# Sheet1.net
KiCad netlist of a schematic drawn in Altium Designer
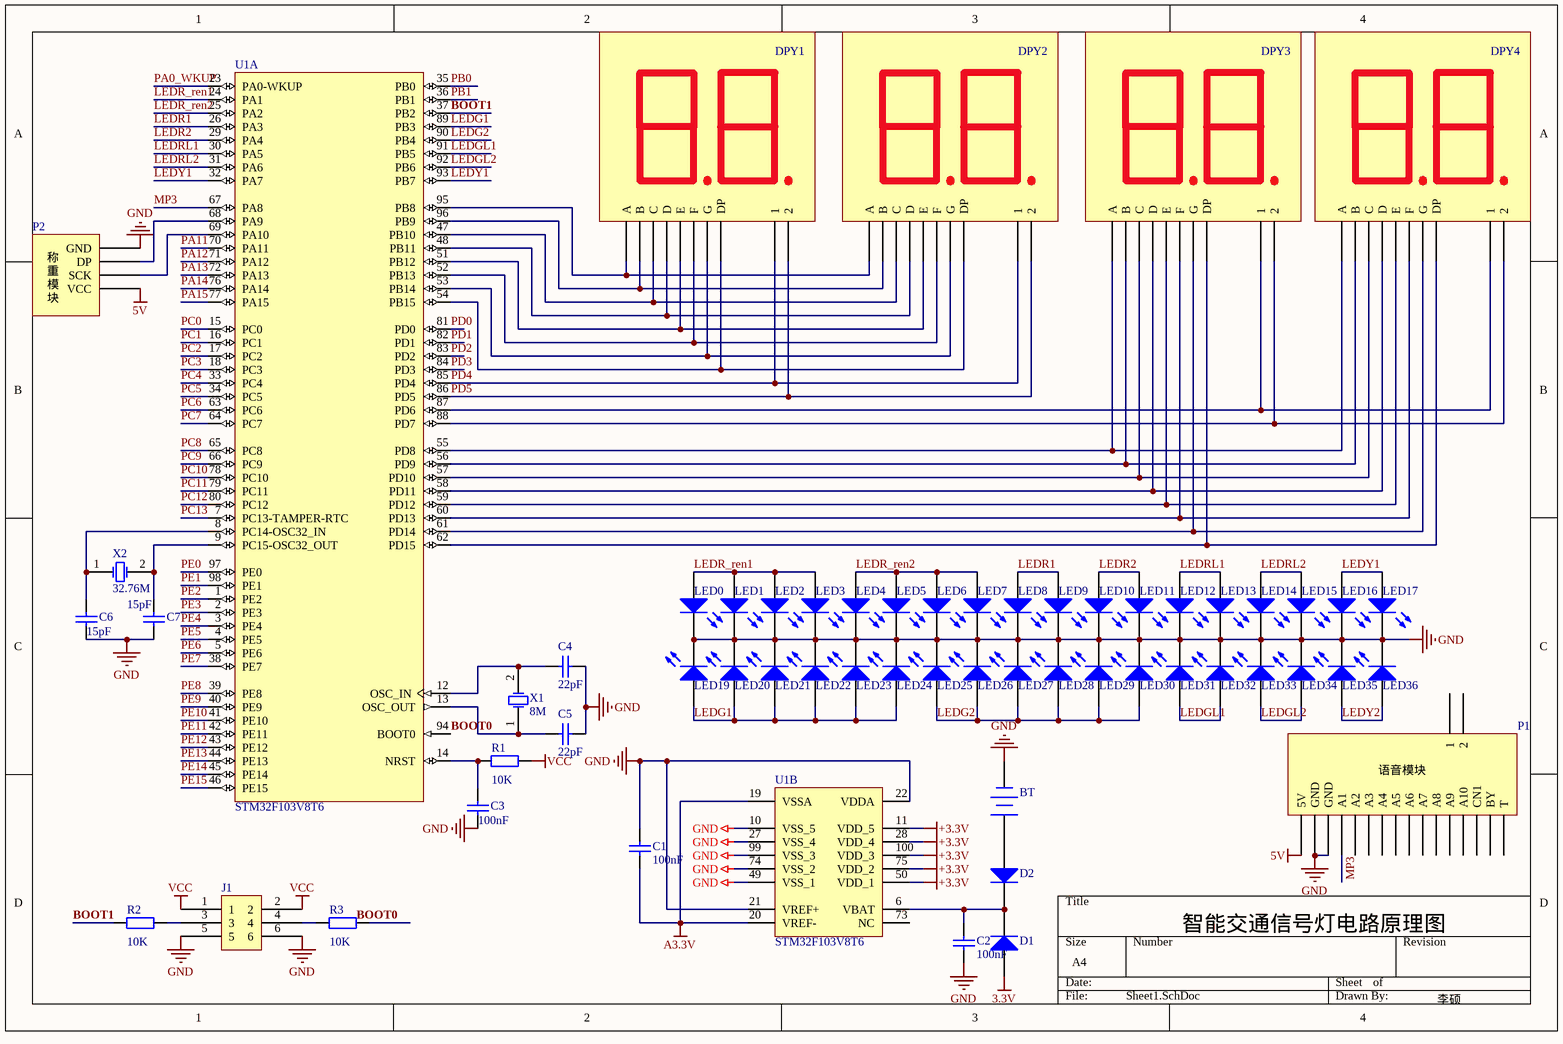
[diagram p0: Sheet1.SchDoc]

(export (version "E")
  (design (tool "Eeschema 10.0.6"))
  (components
    (comp (ref "BT")
      (value "Battery")
      (footprint "BAT-2")
      (description "Multicell Battery")
      (fields (field (name "PUBLISHER") "Altium Limited"))
      (libsource (lib "Miscellaneous Devices") (part "Battery"))
    )
    (comp (ref "C1")
      (value "100nF")
      (footprint "RAD-0.3")
      (description "Capacitor")
      (fields (field (name "Comment") "Cap") (field (name "PUBLISHER") "Altium Limited"))
      (libsource (lib "Miscellaneous Devices") (part "Cap"))
    )
    (comp (ref "C2")
      (value "100nF")
      (footprint "RAD-0.3")
      (description "Capacitor")
      (fields (field (name "Comment") "Cap") (field (name "PUBLISHER") "Altium Limited"))
      (libsource (lib "Miscellaneous Devices") (part "Cap"))
    )
    (comp (ref "C3")
      (value "100nF")
      (footprint "RAD-0.3")
      (description "Capacitor")
      (fields (field (name "Comment") "Cap") (field (name "PUBLISHER") "Altium Limited"))
      (libsource (lib "Miscellaneous Devices") (part "Cap"))
    )
    (comp (ref "C4")
      (value "22pF")
      (footprint "RAD-0.3")
      (description "Capacitor")
      (fields (field (name "Comment") "Cap") (field (name "PUBLISHER") "Altium Limited"))
      (libsource (lib "Miscellaneous Devices") (part "Cap"))
    )
    (comp (ref "C5")
      (value "22pF")
      (footprint "RAD-0.3")
      (description "Capacitor")
      (fields (field (name "Comment") "Cap") (field (name "PUBLISHER") "Altium Limited"))
      (libsource (lib "Miscellaneous Devices") (part "Cap"))
    )
    (comp (ref "C6")
      (value "15pF")
      (footprint "RAD-0.3")
      (description "Capacitor")
      (fields (field (name "Comment") "Cap") (field (name "PUBLISHER") "Altium Limited"))
      (libsource (lib "Miscellaneous Devices") (part "Cap"))
    )
    (comp (ref "C7")
      (value "15pF")
      (footprint "RAD-0.3")
      (description "Capacitor")
      (fields (field (name "Comment") "Cap") (field (name "PUBLISHER") "Altium Limited"))
      (libsource (lib "Miscellaneous Devices") (part "Cap"))
    )
    (comp (ref "D1")
      (value "Diode")
      (footprint "DSO-C2/X3.3")
      (description "Default Diode")
      (fields (field (name "PUBLISHER") "Altium Limited"))
      (libsource (lib "Miscellaneous Devices") (part "Diode"))
    )
    (comp (ref "D2")
      (value "Diode")
      (footprint "DSO-C2/X3.3")
      (description "Default Diode")
      (fields (field (name "PUBLISHER") "Altium Limited"))
      (libsource (lib "Miscellaneous Devices") (part "Diode"))
    )
    (comp (ref "DPY1") (value "Component_1") (libsource (lib "Schlib1") (part "Component_1")))
    (comp (ref "DPY2") (value "Component_1") (libsource (lib "Schlib1") (part "Component_1")))
    (comp (ref "DPY3") (value "Component_1") (libsource (lib "Schlib1") (part "Component_1")))
    (comp (ref "DPY4") (value "Component_1") (libsource (lib "Schlib1") (part "Component_1")))
    (comp (ref "J1") (value "Component_1") (libsource (lib "") (part "Component_1_1")))
    (comp (ref "LED0")
      (value "LED0")
      (footprint "LED-0")
      (description "Typical INFRARED GaAs LED")
      (fields (field (name "PUBLISHER") "Altium Limited"))
      (libsource (lib "Miscellaneous Devices") (part "LED0"))
    )
    (comp (ref "LED1")
      (value "LED0")
      (footprint "LED-0")
      (description "Typical INFRARED GaAs LED")
      (fields (field (name "PUBLISHER") "Altium Limited"))
      (libsource (lib "Miscellaneous Devices") (part "LED0"))
    )
    (comp (ref "LED2")
      (value "LED0")
      (footprint "LED-0")
      (description "Typical INFRARED GaAs LED")
      (fields (field (name "PUBLISHER") "Altium Limited"))
      (libsource (lib "Miscellaneous Devices") (part "LED0"))
    )
    (comp (ref "LED3")
      (value "LED0")
      (footprint "LED-0")
      (description "Typical INFRARED GaAs LED")
      (fields (field (name "PUBLISHER") "Altium Limited"))
      (libsource (lib "Miscellaneous Devices") (part "LED0"))
    )
    (comp (ref "LED4")
      (value "LED0")
      (footprint "LED-0")
      (description "Typical INFRARED GaAs LED")
      (fields (field (name "PUBLISHER") "Altium Limited"))
      (libsource (lib "Miscellaneous Devices") (part "LED0"))
    )
    (comp (ref "LED5")
      (value "LED0")
      (footprint "LED-0")
      (description "Typical INFRARED GaAs LED")
      (fields (field (name "PUBLISHER") "Altium Limited"))
      (libsource (lib "Miscellaneous Devices") (part "LED0"))
    )
    (comp (ref "LED6")
      (value "LED0")
      (footprint "LED-0")
      (description "Typical INFRARED GaAs LED")
      (fields (field (name "PUBLISHER") "Altium Limited"))
      (libsource (lib "Miscellaneous Devices") (part "LED0"))
    )
    (comp (ref "LED7")
      (value "LED0")
      (footprint "LED-0")
      (description "Typical INFRARED GaAs LED")
      (fields (field (name "PUBLISHER") "Altium Limited"))
      (libsource (lib "Miscellaneous Devices") (part "LED0"))
    )
    (comp (ref "LED8")
      (value "LED0")
      (footprint "LED-0")
      (description "Typical INFRARED GaAs LED")
      (fields (field (name "PUBLISHER") "Altium Limited"))
      (libsource (lib "Miscellaneous Devices") (part "LED0"))
    )
    (comp (ref "LED9")
      (value "LED0")
      (footprint "LED-0")
      (description "Typical INFRARED GaAs LED")
      (fields (field (name "PUBLISHER") "Altium Limited"))
      (libsource (lib "Miscellaneous Devices") (part "LED0"))
    )
    (comp (ref "LED10")
      (value "LED0")
      (footprint "LED-0")
      (description "Typical INFRARED GaAs LED")
      (fields (field (name "PUBLISHER") "Altium Limited"))
      (libsource (lib "Miscellaneous Devices") (part "LED0"))
    )
    (comp (ref "LED11")
      (value "LED0")
      (footprint "LED-0")
      (description "Typical INFRARED GaAs LED")
      (fields (field (name "PUBLISHER") "Altium Limited"))
      (libsource (lib "Miscellaneous Devices") (part "LED0"))
    )
    (comp (ref "LED12")
      (value "LED0")
      (footprint "LED-0")
      (description "Typical INFRARED GaAs LED")
      (fields (field (name "PUBLISHER") "Altium Limited"))
      (libsource (lib "Miscellaneous Devices") (part "LED0"))
    )
    (comp (ref "LED13")
      (value "LED0")
      (footprint "LED-0")
      (description "Typical INFRARED GaAs LED")
      (fields (field (name "PUBLISHER") "Altium Limited"))
      (libsource (lib "Miscellaneous Devices") (part "LED0"))
    )
    (comp (ref "LED14")
      (value "LED0")
      (footprint "LED-0")
      (description "Typical INFRARED GaAs LED")
      (fields (field (name "PUBLISHER") "Altium Limited"))
      (libsource (lib "Miscellaneous Devices") (part "LED0"))
    )
    (comp (ref "LED15")
      (value "LED0")
      (footprint "LED-0")
      (description "Typical INFRARED GaAs LED")
      (fields (field (name "PUBLISHER") "Altium Limited"))
      (libsource (lib "Miscellaneous Devices") (part "LED0"))
    )
    (comp (ref "LED16")
      (value "LED0")
      (footprint "LED-0")
      (description "Typical INFRARED GaAs LED")
      (fields (field (name "PUBLISHER") "Altium Limited"))
      (libsource (lib "Miscellaneous Devices") (part "LED0"))
    )
    (comp (ref "LED17")
      (value "LED0")
      (footprint "LED-0")
      (description "Typical INFRARED GaAs LED")
      (fields (field (name "PUBLISHER") "Altium Limited"))
      (libsource (lib "Miscellaneous Devices") (part "LED0"))
    )
    (comp (ref "LED19")
      (value "LED0")
      (footprint "LED-0")
      (description "Typical INFRARED GaAs LED")
      (fields (field (name "PUBLISHER") "Altium Limited"))
      (libsource (lib "Miscellaneous Devices") (part "LED0"))
    )
    (comp (ref "LED20")
      (value "LED0")
      (footprint "LED-0")
      (description "Typical INFRARED GaAs LED")
      (fields (field (name "PUBLISHER") "Altium Limited"))
      (libsource (lib "Miscellaneous Devices") (part "LED0"))
    )
    (comp (ref "LED21")
      (value "LED0")
      (footprint "LED-0")
      (description "Typical INFRARED GaAs LED")
      (fields (field (name "PUBLISHER") "Altium Limited"))
      (libsource (lib "Miscellaneous Devices") (part "LED0"))
    )
    (comp (ref "LED22")
      (value "LED0")
      (footprint "LED-0")
      (description "Typical INFRARED GaAs LED")
      (fields (field (name "PUBLISHER") "Altium Limited"))
      (libsource (lib "Miscellaneous Devices") (part "LED0"))
    )
    (comp (ref "LED23")
      (value "LED0")
      (footprint "LED-0")
      (description "Typical INFRARED GaAs LED")
      (fields (field (name "PUBLISHER") "Altium Limited"))
      (libsource (lib "Miscellaneous Devices") (part "LED0"))
    )
    (comp (ref "LED24")
      (value "LED0")
      (footprint "LED-0")
      (description "Typical INFRARED GaAs LED")
      (fields (field (name "PUBLISHER") "Altium Limited"))
      (libsource (lib "Miscellaneous Devices") (part "LED0"))
    )
    (comp (ref "LED25")
      (value "LED0")
      (footprint "LED-0")
      (description "Typical INFRARED GaAs LED")
      (fields (field (name "PUBLISHER") "Altium Limited"))
      (libsource (lib "Miscellaneous Devices") (part "LED0"))
    )
    (comp (ref "LED26")
      (value "LED0")
      (footprint "LED-0")
      (description "Typical INFRARED GaAs LED")
      (fields (field (name "PUBLISHER") "Altium Limited"))
      (libsource (lib "Miscellaneous Devices") (part "LED0"))
    )
    (comp (ref "LED27")
      (value "LED0")
      (footprint "LED-0")
      (description "Typical INFRARED GaAs LED")
      (fields (field (name "PUBLISHER") "Altium Limited"))
      (libsource (lib "Miscellaneous Devices") (part "LED0"))
    )
    (comp (ref "LED28")
      (value "LED0")
      (footprint "LED-0")
      (description "Typical INFRARED GaAs LED")
      (fields (field (name "PUBLISHER") "Altium Limited"))
      (libsource (lib "Miscellaneous Devices") (part "LED0"))
    )
    (comp (ref "LED29")
      (value "LED0")
      (footprint "LED-0")
      (description "Typical INFRARED GaAs LED")
      (fields (field (name "PUBLISHER") "Altium Limited"))
      (libsource (lib "Miscellaneous Devices") (part "LED0"))
    )
    (comp (ref "LED30")
      (value "LED0")
      (footprint "LED-0")
      (description "Typical INFRARED GaAs LED")
      (fields (field (name "PUBLISHER") "Altium Limited"))
      (libsource (lib "Miscellaneous Devices") (part "LED0"))
    )
    (comp (ref "LED31")
      (value "LED0")
      (footprint "LED-0")
      (description "Typical INFRARED GaAs LED")
      (fields (field (name "PUBLISHER") "Altium Limited"))
      (libsource (lib "Miscellaneous Devices") (part "LED0"))
    )
    (comp (ref "LED32")
      (value "LED0")
      (footprint "LED-0")
      (description "Typical INFRARED GaAs LED")
      (fields (field (name "PUBLISHER") "Altium Limited"))
      (libsource (lib "Miscellaneous Devices") (part "LED0"))
    )
    (comp (ref "LED33")
      (value "LED0")
      (footprint "LED-0")
      (description "Typical INFRARED GaAs LED")
      (fields (field (name "PUBLISHER") "Altium Limited"))
      (libsource (lib "Miscellaneous Devices") (part "LED0"))
    )
    (comp (ref "LED34")
      (value "LED0")
      (footprint "LED-0")
      (description "Typical INFRARED GaAs LED")
      (fields (field (name "PUBLISHER") "Altium Limited"))
      (libsource (lib "Miscellaneous Devices") (part "LED0"))
    )
    (comp (ref "LED35")
      (value "LED0")
      (footprint "LED-0")
      (description "Typical INFRARED GaAs LED")
      (fields (field (name "PUBLISHER") "Altium Limited"))
      (libsource (lib "Miscellaneous Devices") (part "LED0"))
    )
    (comp (ref "LED36")
      (value "LED0")
      (footprint "LED-0")
      (description "Typical INFRARED GaAs LED")
      (fields (field (name "PUBLISHER") "Altium Limited"))
      (libsource (lib "Miscellaneous Devices") (part "LED0"))
    )
    (comp (ref "P1") (value "Component_2") (libsource (lib "Schlib1") (part "Component_2")))
    (comp (ref "P2") (value "HX711AD") (libsource (lib "Schlib1") (part "Component_3")))
    (comp (ref "R1")
      (value "10K")
      (footprint "AXIAL-0.4")
      (description "Resistor")
      (fields (field (name "Comment") "Res2") (field (name "PUBLISHER") "Altium Limited"))
      (libsource (lib "Miscellaneous Devices") (part "Res2"))
    )
    (comp (ref "R2")
      (value "10K")
      (footprint "AXIAL-0.4")
      (description "Resistor")
      (fields (field (name "Comment") "Res2") (field (name "PUBLISHER") "Altium Limited"))
      (libsource (lib "Miscellaneous Devices") (part "Res2"))
    )
    (comp (ref "R3")
      (value "10K")
      (footprint "AXIAL-0.4")
      (description "Resistor")
      (fields (field (name "Comment") "Res2") (field (name "PUBLISHER") "Altium Limited"))
      (libsource (lib "Miscellaneous Devices") (part "Res2"))
    )
    (comp (ref "U1")
      (value "STM32F103V8T6")
      (footprint "LQFP100_N")
      (libsource (lib "") (part "STM32F103V8T6_1"))
    )
    (comp (ref "X1")
      (value "8M")
      (footprint "BCY-W2/D3.1")
      (description "Crystal Oscillator")
      (fields (field (name "PUBLISHER") "Altium Limited"))
      (libsource (lib "Miscellaneous Devices") (part "XTAL"))
    )
    (comp (ref "X2")
      (value "32.76M")
      (footprint "BCY-W2/D3.1")
      (description "Crystal Oscillator")
      (fields (field (name "PUBLISHER") "Altium Limited"))
      (libsource (lib "Miscellaneous Devices") (part "XTAL"))
    )
  )
  (nets
    (net (code "1") (name "+3.3V") (class "Default")
      (node (ref "U1") (pin "100") (pinfunction "VDD_3_100") (pintype "power_in"))
      (node (ref "U1") (pin "11") (pinfunction "VDD_5_11") (pintype "power_in"))
      (node (ref "U1") (pin "28") (pinfunction "VDD_4_28") (pintype "power_in"))
      (node (ref "U1") (pin "50") (pinfunction "VDD_1_50") (pintype "power_in"))
      (node (ref "U1") (pin "75") (pinfunction "VDD_2_75") (pintype "power_in"))
    )
    (net (code "2") (name "/BOOT0") (class "Default")
      (node (ref "U1") (pin "94") (pinfunction "BOOT0_94") (pintype "input"))
    )
    (net (code "3") (name "/BOOT1") (class "Default")
      (node (ref "R2") (pin "1") (pinfunction "1_1") (pintype "passive"))
      (node (ref "U1") (pin "37") (pinfunction "PB2_37") (pintype "bidirectional"))
    )
    (net (code "4") (name "/LEDG1") (class "Default")
      (node (ref "LED19") (pin "1") (pinfunction "A_1") (pintype "passive"))
      (node (ref "LED20") (pin "1") (pinfunction "A_1") (pintype "passive"))
      (node (ref "LED21") (pin "1") (pinfunction "A_1") (pintype "passive"))
      (node (ref "LED22") (pin "1") (pinfunction "A_1") (pintype "passive"))
      (node (ref "LED23") (pin "1") (pinfunction "A_1") (pintype "passive"))
      (node (ref "LED24") (pin "1") (pinfunction "A_1") (pintype "passive"))
      (node (ref "U1") (pin "89") (pinfunction "PB3_89") (pintype "bidirectional"))
    )
    (net (code "5") (name "/LEDG2") (class "Default")
      (node (ref "LED25") (pin "1") (pinfunction "A_1") (pintype "passive"))
      (node (ref "LED26") (pin "1") (pinfunction "A_1") (pintype "passive"))
      (node (ref "LED27") (pin "1") (pinfunction "A_1") (pintype "passive"))
      (node (ref "LED28") (pin "1") (pinfunction "A_1") (pintype "passive"))
      (node (ref "LED29") (pin "1") (pinfunction "A_1") (pintype "passive"))
      (node (ref "LED30") (pin "1") (pinfunction "A_1") (pintype "passive"))
      (node (ref "U1") (pin "90") (pinfunction "PB4_90") (pintype "bidirectional"))
    )
    (net (code "6") (name "/LEDGL1") (class "Default")
      (node (ref "LED31") (pin "1") (pinfunction "A_1") (pintype "passive"))
      (node (ref "LED32") (pin "1") (pinfunction "A_1") (pintype "passive"))
      (node (ref "U1") (pin "91") (pinfunction "PB5_91") (pintype "bidirectional"))
    )
    (net (code "7") (name "/LEDGL2") (class "Default")
      (node (ref "LED33") (pin "1") (pinfunction "A_1") (pintype "passive"))
      (node (ref "LED34") (pin "1") (pinfunction "A_1") (pintype "passive"))
      (node (ref "U1") (pin "92") (pinfunction "PB6_92") (pintype "bidirectional"))
    )
    (net (code "8") (name "/LEDR1") (class "Default")
      (node (ref "LED8") (pin "1") (pinfunction "A_1") (pintype "passive"))
      (node (ref "LED9") (pin "1") (pinfunction "A_1") (pintype "passive"))
      (node (ref "U1") (pin "26") (pinfunction "PA3_26") (pintype "bidirectional"))
    )
    (net (code "9") (name "/LEDR2") (class "Default")
      (node (ref "LED10") (pin "1") (pinfunction "A_1") (pintype "passive"))
      (node (ref "LED11") (pin "1") (pinfunction "A_1") (pintype "passive"))
      (node (ref "U1") (pin "29") (pinfunction "PA4_29") (pintype "bidirectional"))
    )
    (net (code "10") (name "/LEDRL1") (class "Default")
      (node (ref "LED12") (pin "1") (pinfunction "A_1") (pintype "passive"))
      (node (ref "LED13") (pin "1") (pinfunction "A_1") (pintype "passive"))
      (node (ref "U1") (pin "30") (pinfunction "PA5_30") (pintype "bidirectional"))
    )
    (net (code "11") (name "/LEDRL2") (class "Default")
      (node (ref "LED14") (pin "1") (pinfunction "A_1") (pintype "passive"))
      (node (ref "LED15") (pin "1") (pinfunction "A_1") (pintype "passive"))
      (node (ref "U1") (pin "31") (pinfunction "PA6_31") (pintype "bidirectional"))
    )
    (net (code "12") (name "/LEDR_ren1") (class "Default")
      (node (ref "LED0") (pin "1") (pinfunction "A_1") (pintype "passive"))
      (node (ref "LED1") (pin "1") (pinfunction "A_1") (pintype "passive"))
      (node (ref "LED2") (pin "1") (pinfunction "A_1") (pintype "passive"))
      (node (ref "LED3") (pin "1") (pinfunction "A_1") (pintype "passive"))
      (node (ref "U1") (pin "24") (pinfunction "PA1_24") (pintype "bidirectional"))
    )
    (net (code "13") (name "/LEDR_ren2") (class "Default")
      (node (ref "LED4") (pin "1") (pinfunction "A_1") (pintype "passive"))
      (node (ref "LED5") (pin "1") (pinfunction "A_1") (pintype "passive"))
      (node (ref "LED6") (pin "1") (pinfunction "A_1") (pintype "passive"))
      (node (ref "LED7") (pin "1") (pinfunction "A_1") (pintype "passive"))
      (node (ref "U1") (pin "25") (pinfunction "PA2_25") (pintype "bidirectional"))
    )
    (net (code "14") (name "/LEDY1") (class "Default")
      (node (ref "LED16") (pin "1") (pinfunction "A_1") (pintype "passive"))
      (node (ref "LED17") (pin "1") (pinfunction "A_1") (pintype "passive"))
      (node (ref "U1") (pin "32") (pinfunction "PA7_32") (pintype "bidirectional"))
      (node (ref "U1") (pin "93") (pinfunction "PB7_93") (pintype "bidirectional"))
    )
    (net (code "15") (name "/LEDY2") (class "Default")
      (node (ref "LED35") (pin "1") (pinfunction "A_1") (pintype "passive"))
      (node (ref "LED36") (pin "1") (pinfunction "A_1") (pintype "passive"))
    )
    (net (code "16") (name "/MP3") (class "Default")
      (node (ref "P1") (pin "PVIN") (pinfunction "A1_PVIN") (pintype "passive"))
      (node (ref "U1") (pin "67") (pinfunction "PA8_67") (pintype "bidirectional"))
    )
    (net (code "17") (name "/PA0_WKUP") (class "Default")
      (node (ref "U1") (pin "23") (pinfunction "PA0-WKUP_23") (pintype "bidirectional"))
    )
    (net (code "18") (name "/PA11") (class "Default")
      (node (ref "U1") (pin "70") (pinfunction "PA11_70") (pintype "bidirectional"))
    )
    (net (code "19") (name "/PA12") (class "Default")
      (node (ref "U1") (pin "71") (pinfunction "PA12_71") (pintype "bidirectional"))
    )
    (net (code "20") (name "/PA13") (class "Default")
      (node (ref "U1") (pin "72") (pinfunction "PA13_72") (pintype "bidirectional"))
    )
    (net (code "21") (name "/PA14") (class "Default")
      (node (ref "U1") (pin "76") (pinfunction "PA14_76") (pintype "bidirectional"))
    )
    (net (code "22") (name "/PA15") (class "Default")
      (node (ref "U1") (pin "77") (pinfunction "PA15_77") (pintype "bidirectional"))
    )
    (net (code "23") (name "/PB0") (class "Default")
      (node (ref "U1") (pin "35") (pinfunction "PB0_35") (pintype "bidirectional"))
    )
    (net (code "24") (name "/PB1") (class "Default")
      (node (ref "U1") (pin "36") (pinfunction "PB1_36") (pintype "bidirectional"))
    )
    (net (code "25") (name "/PC0") (class "Default")
      (node (ref "U1") (pin "15") (pinfunction "PC0_15") (pintype "bidirectional"))
    )
    (net (code "26") (name "/PC1") (class "Default")
      (node (ref "U1") (pin "16") (pinfunction "PC1_16") (pintype "bidirectional"))
    )
    (net (code "27") (name "/PC2") (class "Default")
      (node (ref "U1") (pin "17") (pinfunction "PC2_17") (pintype "bidirectional"))
    )
    (net (code "28") (name "/PC3") (class "Default")
      (node (ref "U1") (pin "18") (pinfunction "PC3_18") (pintype "bidirectional"))
    )
    (net (code "29") (name "/PC4") (class "Default")
      (node (ref "U1") (pin "33") (pinfunction "PC4_33") (pintype "bidirectional"))
    )
    (net (code "30") (name "/PC5") (class "Default")
      (node (ref "U1") (pin "34") (pinfunction "PC5_34") (pintype "bidirectional"))
    )
    (net (code "31") (name "/PC6") (class "Default")
      (node (ref "U1") (pin "63") (pinfunction "PC6_63") (pintype "bidirectional"))
    )
    (net (code "32") (name "/PC7") (class "Default")
      (node (ref "U1") (pin "64") (pinfunction "PC7_64") (pintype "bidirectional"))
    )
    (net (code "33") (name "/PC8") (class "Default")
      (node (ref "U1") (pin "65") (pinfunction "PC8_65") (pintype "bidirectional"))
    )
    (net (code "34") (name "/PC9") (class "Default")
      (node (ref "U1") (pin "66") (pinfunction "PC9_66") (pintype "bidirectional"))
    )
    (net (code "35") (name "/PC10") (class "Default")
      (node (ref "U1") (pin "78") (pinfunction "PC10_78") (pintype "bidirectional"))
    )
    (net (code "36") (name "/PC11") (class "Default")
      (node (ref "U1") (pin "79") (pinfunction "PC11_79") (pintype "bidirectional"))
    )
    (net (code "37") (name "/PC12") (class "Default")
      (node (ref "U1") (pin "80") (pinfunction "PC12_80") (pintype "bidirectional"))
    )
    (net (code "38") (name "/PC13") (class "Default")
      (node (ref "U1") (pin "7") (pinfunction "PC13-TAMPER-RTC_7") (pintype "bidirectional"))
    )
    (net (code "39") (name "/PD0") (class "Default")
      (node (ref "U1") (pin "81") (pinfunction "PD0_81") (pintype "bidirectional"))
    )
    (net (code "40") (name "/PD1") (class "Default")
      (node (ref "U1") (pin "82") (pinfunction "PD1_82") (pintype "bidirectional"))
    )
    (net (code "41") (name "/PD2") (class "Default")
      (node (ref "U1") (pin "83") (pinfunction "PD2_83") (pintype "bidirectional"))
    )
    (net (code "42") (name "/PD3") (class "Default")
      (node (ref "U1") (pin "84") (pinfunction "PD3_84") (pintype "bidirectional"))
    )
    (net (code "43") (name "/PD4") (class "Default")
      (node (ref "DPY1") (pin "PVIN") (pinfunction "1_PVIN") (pintype "passive"))
      (node (ref "DPY2") (pin "PVIN") (pinfunction "1_PVIN") (pintype "passive"))
      (node (ref "U1") (pin "85") (pinfunction "PD4_85") (pintype "bidirectional"))
    )
    (net (code "44") (name "/PD5") (class "Default")
      (node (ref "DPY1") (pin "PVIN") (pinfunction "2_PVIN") (pintype "passive"))
      (node (ref "DPY2") (pin "PVIN") (pinfunction "2_PVIN") (pintype "passive"))
      (node (ref "U1") (pin "86") (pinfunction "PD5_86") (pintype "bidirectional"))
    )
    (net (code "45") (name "/PE0") (class "Default")
      (node (ref "U1") (pin "97") (pinfunction "PE0_97") (pintype "bidirectional"))
    )
    (net (code "46") (name "/PE1") (class "Default")
      (node (ref "U1") (pin "98") (pinfunction "PE1_98") (pintype "bidirectional"))
    )
    (net (code "47") (name "/PE2") (class "Default")
      (node (ref "U1") (pin "1") (pinfunction "PE2_1") (pintype "bidirectional"))
    )
    (net (code "48") (name "/PE3") (class "Default")
      (node (ref "U1") (pin "2") (pinfunction "PE3_2") (pintype "bidirectional"))
    )
    (net (code "49") (name "/PE4") (class "Default")
      (node (ref "U1") (pin "3") (pinfunction "PE4_3") (pintype "bidirectional"))
    )
    (net (code "50") (name "/PE5") (class "Default")
      (node (ref "U1") (pin "4") (pinfunction "PE5_4") (pintype "bidirectional"))
    )
    (net (code "51") (name "/PE6") (class "Default")
      (node (ref "U1") (pin "5") (pinfunction "PE6_5") (pintype "bidirectional"))
    )
    (net (code "52") (name "/PE7") (class "Default")
      (node (ref "U1") (pin "38") (pinfunction "PE7_38") (pintype "bidirectional"))
    )
    (net (code "53") (name "/PE8") (class "Default")
      (node (ref "U1") (pin "39") (pinfunction "PE8_39") (pintype "bidirectional"))
    )
    (net (code "54") (name "/PE9") (class "Default")
      (node (ref "U1") (pin "40") (pinfunction "PE9_40") (pintype "bidirectional"))
    )
    (net (code "55") (name "/PE10") (class "Default")
      (node (ref "U1") (pin "41") (pinfunction "PE10_41") (pintype "bidirectional"))
    )
    (net (code "56") (name "/PE11") (class "Default")
      (node (ref "U1") (pin "42") (pinfunction "PE11_42") (pintype "bidirectional"))
    )
    (net (code "57") (name "/PE12") (class "Default")
      (node (ref "U1") (pin "43") (pinfunction "PE12_43") (pintype "bidirectional"))
    )
    (net (code "58") (name "/PE13") (class "Default")
      (node (ref "U1") (pin "44") (pinfunction "PE13_44") (pintype "bidirectional"))
    )
    (net (code "59") (name "/PE14") (class "Default")
      (node (ref "U1") (pin "45") (pinfunction "PE14_45") (pintype "bidirectional"))
    )
    (net (code "60") (name "/PE15") (class "Default")
      (node (ref "U1") (pin "46") (pinfunction "PE15_46") (pintype "bidirectional"))
    )
    (net (code "61") (name "3.3V") (class "Default")
      (node (ref "D1") (pin "1") (pinfunction "A_1") (pintype "passive"))
    )
    (net (code "62") (name "5V") (class "Default")
      (node (ref "P1") (pin "PVIN") (pinfunction "5V_PVIN") (pintype "passive"))
      (node (ref "P2") (pin "PVIN") (pinfunction "VCC_PVIN") (pintype "passive"))
    )
    (net (code "63") (name "A3.3V") (class "Default")
      (node (ref "C1") (pin "2") (pinfunction "2_2") (pintype "passive"))
      (node (ref "U1") (pin "19") (pinfunction "VSSA_19") (pintype "power_in"))
      (node (ref "U1") (pin "20") (pinfunction "VREF-_20") (pintype "power_in"))
    )
    (net (code "64") (name "GND") (class "Default")
      (node (ref "BT") (pin "2") (pinfunction "-_2") (pintype "passive"))
      (node (ref "C1") (pin "1") (pinfunction "1_1") (pintype "passive"))
      (node (ref "C2") (pin "2") (pinfunction "2_2") (pintype "passive"))
      (node (ref "C3") (pin "1") (pinfunction "1_1") (pintype "passive"))
      (node (ref "C4") (pin "1") (pinfunction "1_1") (pintype "passive"))
      (node (ref "C5") (pin "1") (pinfunction "1_1") (pintype "passive"))
      (node (ref "C6") (pin "1") (pinfunction "1_1") (pintype "passive"))
      (node (ref "C7") (pin "1") (pinfunction "1_1") (pintype "passive"))
      (node (ref "J1") (pin "5") (pinfunction "5_5") (pintype "passive"))
      (node (ref "J1") (pin "6") (pinfunction "6_6") (pintype "passive"))
      (node (ref "LED0") (pin "2") (pinfunction "K_2") (pintype "passive"))
      (node (ref "LED1") (pin "2") (pinfunction "K_2") (pintype "passive"))
      (node (ref "LED10") (pin "2") (pinfunction "K_2") (pintype "passive"))
      (node (ref "LED11") (pin "2") (pinfunction "K_2") (pintype "passive"))
      (node (ref "LED12") (pin "2") (pinfunction "K_2") (pintype "passive"))
      (node (ref "LED13") (pin "2") (pinfunction "K_2") (pintype "passive"))
      (node (ref "LED14") (pin "2") (pinfunction "K_2") (pintype "passive"))
      (node (ref "LED15") (pin "2") (pinfunction "K_2") (pintype "passive"))
      (node (ref "LED16") (pin "2") (pinfunction "K_2") (pintype "passive"))
      (node (ref "LED17") (pin "2") (pinfunction "K_2") (pintype "passive"))
      (node (ref "LED19") (pin "2") (pinfunction "K_2") (pintype "passive"))
      (node (ref "LED2") (pin "2") (pinfunction "K_2") (pintype "passive"))
      (node (ref "LED20") (pin "2") (pinfunction "K_2") (pintype "passive"))
      (node (ref "LED21") (pin "2") (pinfunction "K_2") (pintype "passive"))
      (node (ref "LED22") (pin "2") (pinfunction "K_2") (pintype "passive"))
      (node (ref "LED23") (pin "2") (pinfunction "K_2") (pintype "passive"))
      (node (ref "LED24") (pin "2") (pinfunction "K_2") (pintype "passive"))
      (node (ref "LED25") (pin "2") (pinfunction "K_2") (pintype "passive"))
      (node (ref "LED26") (pin "2") (pinfunction "K_2") (pintype "passive"))
      (node (ref "LED27") (pin "2") (pinfunction "K_2") (pintype "passive"))
      (node (ref "LED28") (pin "2") (pinfunction "K_2") (pintype "passive"))
      (node (ref "LED29") (pin "2") (pinfunction "K_2") (pintype "passive"))
      (node (ref "LED3") (pin "2") (pinfunction "K_2") (pintype "passive"))
      (node (ref "LED30") (pin "2") (pinfunction "K_2") (pintype "passive"))
      (node (ref "LED31") (pin "2") (pinfunction "K_2") (pintype "passive"))
      (node (ref "LED32") (pin "2") (pinfunction "K_2") (pintype "passive"))
      (node (ref "LED33") (pin "2") (pinfunction "K_2") (pintype "passive"))
      (node (ref "LED34") (pin "2") (pinfunction "K_2") (pintype "passive"))
      (node (ref "LED35") (pin "2") (pinfunction "K_2") (pintype "passive"))
      (node (ref "LED36") (pin "2") (pinfunction "K_2") (pintype "passive"))
      (node (ref "LED4") (pin "2") (pinfunction "K_2") (pintype "passive"))
      (node (ref "LED5") (pin "2") (pinfunction "K_2") (pintype "passive"))
      (node (ref "LED6") (pin "2") (pinfunction "K_2") (pintype "passive"))
      (node (ref "LED7") (pin "2") (pinfunction "K_2") (pintype "passive"))
      (node (ref "LED8") (pin "2") (pinfunction "K_2") (pintype "passive"))
      (node (ref "LED9") (pin "2") (pinfunction "K_2") (pintype "passive"))
      (node (ref "P1") (pin "PVIN") (pinfunction "GND_PVIN") (pintype "passive"))
      (node (ref "P2") (pin "PVIN") (pinfunction "GND_PVIN") (pintype "passive"))
      (node (ref "U1") (pin "10") (pinfunction "VSS_5_10") (pintype "power_in"))
      (node (ref "U1") (pin "21") (pinfunction "VREF+_21") (pintype "power_in"))
      (node (ref "U1") (pin "22") (pinfunction "VDDA_22") (pintype "power_in"))
      (node (ref "U1") (pin "27") (pinfunction "VSS_4_27") (pintype "power_in"))
      (node (ref "U1") (pin "49") (pinfunction "VSS_1_49") (pintype "power_in"))
      (node (ref "U1") (pin "74") (pinfunction "VSS_2_74") (pintype "power_in"))
      (node (ref "U1") (pin "99") (pinfunction "VSS_3_99") (pintype "power_in"))
    )
    (net (code "65") (name "Net-(BT-+)") (class "Default")
      (node (ref "BT") (pin "1") (pinfunction "+_1") (pintype "passive"))
      (node (ref "D2") (pin "1") (pinfunction "A_1") (pintype "passive"))
    )
    (net (code "66") (name "Net-(D1-K)") (class "Default")
      (node (ref "C2") (pin "1") (pinfunction "1_1") (pintype "passive"))
      (node (ref "D1") (pin "2") (pinfunction "K_2") (pintype "passive"))
      (node (ref "D2") (pin "2") (pinfunction "K_2") (pintype "passive"))
      (node (ref "U1") (pin "6") (pinfunction "VBAT_6") (pintype "power_in"))
    )
    (net (code "67") (name "Net-(DPY1-A)") (class "Default")
      (node (ref "DPY1") (pin "PVIN") (pinfunction "A_PVIN") (pintype "passive"))
      (node (ref "DPY2") (pin "PVIN") (pinfunction "A_PVIN") (pintype "passive"))
      (node (ref "U1") (pin "95") (pinfunction "PB8_95") (pintype "bidirectional"))
    )
    (net (code "68") (name "Net-(DPY1-B)") (class "Default")
      (node (ref "DPY1") (pin "PVIN") (pinfunction "B_PVIN") (pintype "passive"))
      (node (ref "DPY2") (pin "PVIN") (pinfunction "B_PVIN") (pintype "passive"))
      (node (ref "U1") (pin "96") (pinfunction "PB9_96") (pintype "bidirectional"))
    )
    (net (code "69") (name "Net-(DPY1-C)") (class "Default")
      (node (ref "DPY1") (pin "PVIN") (pinfunction "C_PVIN") (pintype "passive"))
      (node (ref "DPY2") (pin "PVIN") (pinfunction "C_PVIN") (pintype "passive"))
      (node (ref "U1") (pin "47") (pinfunction "PB10_47") (pintype "bidirectional"))
    )
    (net (code "70") (name "Net-(DPY1-D)") (class "Default")
      (node (ref "DPY1") (pin "PVIN") (pinfunction "D_PVIN") (pintype "passive"))
      (node (ref "DPY2") (pin "PVIN") (pinfunction "D_PVIN") (pintype "passive"))
      (node (ref "U1") (pin "48") (pinfunction "PB11_48") (pintype "bidirectional"))
    )
    (net (code "71") (name "Net-(DPY1-DP)") (class "Default")
      (node (ref "DPY1") (pin "PVIN") (pinfunction "DP_PVIN") (pintype "passive"))
      (node (ref "DPY2") (pin "PVIN") (pinfunction "DP_PVIN") (pintype "passive"))
      (node (ref "U1") (pin "54") (pinfunction "PB15_54") (pintype "bidirectional"))
    )
    (net (code "72") (name "Net-(DPY1-E)") (class "Default")
      (node (ref "DPY1") (pin "PVIN") (pinfunction "E_PVIN") (pintype "passive"))
      (node (ref "DPY2") (pin "PVIN") (pinfunction "E_PVIN") (pintype "passive"))
      (node (ref "U1") (pin "51") (pinfunction "PB12_51") (pintype "bidirectional"))
    )
    (net (code "73") (name "Net-(DPY1-F)") (class "Default")
      (node (ref "DPY1") (pin "PVIN") (pinfunction "F_PVIN") (pintype "passive"))
      (node (ref "DPY2") (pin "PVIN") (pinfunction "F_PVIN") (pintype "passive"))
      (node (ref "U1") (pin "52") (pinfunction "PB13_52") (pintype "bidirectional"))
    )
    (net (code "74") (name "Net-(DPY1-G)") (class "Default")
      (node (ref "DPY1") (pin "PVIN") (pinfunction "G_PVIN") (pintype "passive"))
      (node (ref "DPY2") (pin "PVIN") (pinfunction "G_PVIN") (pintype "passive"))
      (node (ref "U1") (pin "53") (pinfunction "PB14_53") (pintype "bidirectional"))
    )
    (net (code "75") (name "Net-(DPY3-1)") (class "Default")
      (node (ref "DPY3") (pin "PVIN") (pinfunction "1_PVIN") (pintype "passive"))
      (node (ref "DPY4") (pin "PVIN") (pinfunction "1_PVIN") (pintype "passive"))
      (node (ref "U1") (pin "87") (pinfunction "PD6_87") (pintype "bidirectional"))
    )
    (net (code "76") (name "Net-(DPY3-2)") (class "Default")
      (node (ref "DPY3") (pin "PVIN") (pinfunction "2_PVIN") (pintype "passive"))
      (node (ref "DPY4") (pin "PVIN") (pinfunction "2_PVIN") (pintype "passive"))
      (node (ref "U1") (pin "88") (pinfunction "PD7_88") (pintype "bidirectional"))
    )
    (net (code "77") (name "Net-(DPY3-A)") (class "Default")
      (node (ref "DPY3") (pin "PVIN") (pinfunction "A_PVIN") (pintype "passive"))
      (node (ref "DPY4") (pin "PVIN") (pinfunction "A_PVIN") (pintype "passive"))
      (node (ref "U1") (pin "55") (pinfunction "PD8_55") (pintype "bidirectional"))
    )
    (net (code "78") (name "Net-(DPY3-B)") (class "Default")
      (node (ref "DPY3") (pin "PVIN") (pinfunction "B_PVIN") (pintype "passive"))
      (node (ref "DPY4") (pin "PVIN") (pinfunction "B_PVIN") (pintype "passive"))
      (node (ref "U1") (pin "56") (pinfunction "PD9_56") (pintype "bidirectional"))
    )
    (net (code "79") (name "Net-(DPY3-C)") (class "Default")
      (node (ref "DPY3") (pin "PVIN") (pinfunction "C_PVIN") (pintype "passive"))
      (node (ref "DPY4") (pin "PVIN") (pinfunction "C_PVIN") (pintype "passive"))
      (node (ref "U1") (pin "57") (pinfunction "PD10_57") (pintype "bidirectional"))
    )
    (net (code "80") (name "Net-(DPY3-D)") (class "Default")
      (node (ref "DPY3") (pin "PVIN") (pinfunction "D_PVIN") (pintype "passive"))
      (node (ref "DPY4") (pin "PVIN") (pinfunction "D_PVIN") (pintype "passive"))
      (node (ref "U1") (pin "58") (pinfunction "PD11_58") (pintype "bidirectional"))
    )
    (net (code "81") (name "Net-(DPY3-DP)") (class "Default")
      (node (ref "DPY3") (pin "PVIN") (pinfunction "DP_PVIN") (pintype "passive"))
      (node (ref "DPY4") (pin "PVIN") (pinfunction "DP_PVIN") (pintype "passive"))
      (node (ref "U1") (pin "62") (pinfunction "PD15_62") (pintype "bidirectional"))
    )
    (net (code "82") (name "Net-(DPY3-E)") (class "Default")
      (node (ref "DPY3") (pin "PVIN") (pinfunction "E_PVIN") (pintype "passive"))
      (node (ref "DPY4") (pin "PVIN") (pinfunction "E_PVIN") (pintype "passive"))
      (node (ref "U1") (pin "59") (pinfunction "PD12_59") (pintype "bidirectional"))
    )
    (net (code "83") (name "Net-(DPY3-F)") (class "Default")
      (node (ref "DPY3") (pin "PVIN") (pinfunction "F_PVIN") (pintype "passive"))
      (node (ref "DPY4") (pin "PVIN") (pinfunction "F_PVIN") (pintype "passive"))
      (node (ref "U1") (pin "60") (pinfunction "PD13_60") (pintype "bidirectional"))
    )
    (net (code "84") (name "Net-(DPY3-G)") (class "Default")
      (node (ref "DPY3") (pin "PVIN") (pinfunction "G_PVIN") (pintype "passive"))
      (node (ref "DPY4") (pin "PVIN") (pinfunction "G_PVIN") (pintype "passive"))
      (node (ref "U1") (pin "61") (pinfunction "PD14_61") (pintype "bidirectional"))
    )
    (net (code "85") (name "Net-(J1-Pad3)") (class "Default")
      (node (ref "J1") (pin "3") (pinfunction "3_3") (pintype "passive"))
      (node (ref "R2") (pin "2") (pinfunction "2_2") (pintype "passive"))
    )
    (net (code "86") (name "Net-(J1-Pad4)") (class "Default")
      (node (ref "J1") (pin "4") (pinfunction "4_4") (pintype "passive"))
      (node (ref "R3") (pin "1") (pinfunction "1_1") (pintype "passive"))
    )
    (net (code "87") (name "Net-(P2-DP)") (class "Default")
      (node (ref "P2") (pin "PVIN") (pinfunction "DP_PVIN") (pintype "passive"))
      (node (ref "U1") (pin "68") (pinfunction "PA9_68") (pintype "bidirectional"))
    )
    (net (code "88") (name "Net-(P2-SCK)") (class "Default")
      (node (ref "P2") (pin "PVIN") (pinfunction "SCK_PVIN") (pintype "passive"))
      (node (ref "U1") (pin "69") (pinfunction "PA10_69") (pintype "bidirectional"))
    )
    (net (code "89") (name "Net-(U1A-NRST)") (class "Default")
      (node (ref "C3") (pin "2") (pinfunction "2_2") (pintype "passive"))
      (node (ref "R1") (pin "1") (pinfunction "1_1") (pintype "passive"))
      (node (ref "U1") (pin "14") (pinfunction "NRST_14") (pintype "bidirectional"))
    )
    (net (code "90") (name "Net-(U1A-OSC_IN)") (class "Default")
      (node (ref "C4") (pin "2") (pinfunction "2_2") (pintype "passive"))
      (node (ref "U1") (pin "12") (pinfunction "OSC_IN_12") (pintype "input"))
      (node (ref "X1") (pin "2") (pinfunction "OSC2_2") (pintype "passive"))
    )
    (net (code "91") (name "Net-(U1A-OSC_OUT)") (class "Default")
      (node (ref "C5") (pin "2") (pinfunction "2_2") (pintype "passive"))
      (node (ref "U1") (pin "13") (pinfunction "OSC_OUT_13") (pintype "output"))
      (node (ref "X1") (pin "1") (pinfunction "OSC1_1") (pintype "passive"))
    )
    (net (code "92") (name "Net-(U1A-PC14-OSC32_IN)") (class "Default")
      (node (ref "C6") (pin "2") (pinfunction "2_2") (pintype "passive"))
      (node (ref "U1") (pin "8") (pinfunction "PC14-OSC32_IN_8") (pintype "bidirectional"))
      (node (ref "X2") (pin "1") (pinfunction "OSC1_1") (pintype "passive"))
    )
    (net (code "93") (name "Net-(U1A-PC15-OSC32_OUT)") (class "Default")
      (node (ref "C7") (pin "2") (pinfunction "2_2") (pintype "passive"))
      (node (ref "U1") (pin "9") (pinfunction "PC15-OSC32_OUT_9") (pintype "bidirectional"))
      (node (ref "X2") (pin "2") (pinfunction "OSC2_2") (pintype "passive"))
    )
    (net (code "94") (name "VCC") (class "Default")
      (node (ref "J1") (pin "1") (pinfunction "1_1") (pintype "passive"))
      (node (ref "J1") (pin "2") (pinfunction "2_2") (pintype "passive"))
      (node (ref "R1") (pin "2") (pinfunction "2_2") (pintype "passive"))
    )
    (net (code "95") (name "unconnected-(P1-1-PadPVIN)") (class "Default")
      (node (ref "P1") (pin "PVIN") (pinfunction "1_PVIN") (pintype "passive"))
    )
    (net (code "96") (name "unconnected-(P1-2-PadPVIN)") (class "Default")
      (node (ref "P1") (pin "PVIN") (pinfunction "2_PVIN") (pintype "passive"))
    )
    (net (code "97") (name "unconnected-(P1-A2-PadPVIN)") (class "Default")
      (node (ref "P1") (pin "PVIN") (pinfunction "A2_PVIN") (pintype "passive"))
    )
    (net (code "98") (name "unconnected-(P1-A3-PadPVIN)") (class "Default")
      (node (ref "P1") (pin "PVIN") (pinfunction "A3_PVIN") (pintype "passive"))
    )
    (net (code "99") (name "unconnected-(P1-A4-PadPVIN)") (class "Default")
      (node (ref "P1") (pin "PVIN") (pinfunction "A4_PVIN") (pintype "passive"))
    )
    (net (code "100") (name "unconnected-(P1-A5-PadPVIN)") (class "Default")
      (node (ref "P1") (pin "PVIN") (pinfunction "A5_PVIN") (pintype "passive"))
    )
    (net (code "101") (name "unconnected-(P1-A6-PadPVIN)") (class "Default")
      (node (ref "P1") (pin "PVIN") (pinfunction "A6_PVIN") (pintype "passive"))
    )
    (net (code "102") (name "unconnected-(P1-A7-PadPVIN)") (class "Default")
      (node (ref "P1") (pin "PVIN") (pinfunction "A7_PVIN") (pintype "passive"))
    )
    (net (code "103") (name "unconnected-(P1-A8-PadPVIN)") (class "Default")
      (node (ref "P1") (pin "PVIN") (pinfunction "A8_PVIN") (pintype "passive"))
    )
    (net (code "104") (name "unconnected-(P1-A9-PadPVIN)") (class "Default")
      (node (ref "P1") (pin "PVIN") (pinfunction "A9_PVIN") (pintype "passive"))
    )
    (net (code "105") (name "unconnected-(P1-A10-PadPVIN)") (class "Default")
      (node (ref "P1") (pin "PVIN") (pinfunction "A10_PVIN") (pintype "passive"))
    )
    (net (code "106") (name "unconnected-(P1-BY-PadPVIN)") (class "Default")
      (node (ref "P1") (pin "PVIN") (pinfunction "BY_PVIN") (pintype "passive"))
    )
    (net (code "107") (name "unconnected-(P1-CN1-PadPVIN)") (class "Default")
      (node (ref "P1") (pin "PVIN") (pinfunction "CN1_PVIN") (pintype "passive"))
    )
    (net (code "108") (name "unconnected-(P1-T-PadPVIN)") (class "Default")
      (node (ref "P1") (pin "PVIN") (pinfunction "T_PVIN") (pintype "passive"))
    )
    (net (code "109") (name "unconnected-(R3-Pad2)") (class "Default")
      (node (ref "R3") (pin "2") (pinfunction "2_2") (pintype "passive"))
    )
    (net (code "110") (name "unconnected-(U1B-NC-Pad73)") (class "Default")
      (node (ref "U1") (pin "73") (pinfunction "NC_73") (pintype "passive"))
    )
  )
)
